# 7_can_rc_i2c_analog.net
KiCad netlist of a schematic drawn in Altium Designer
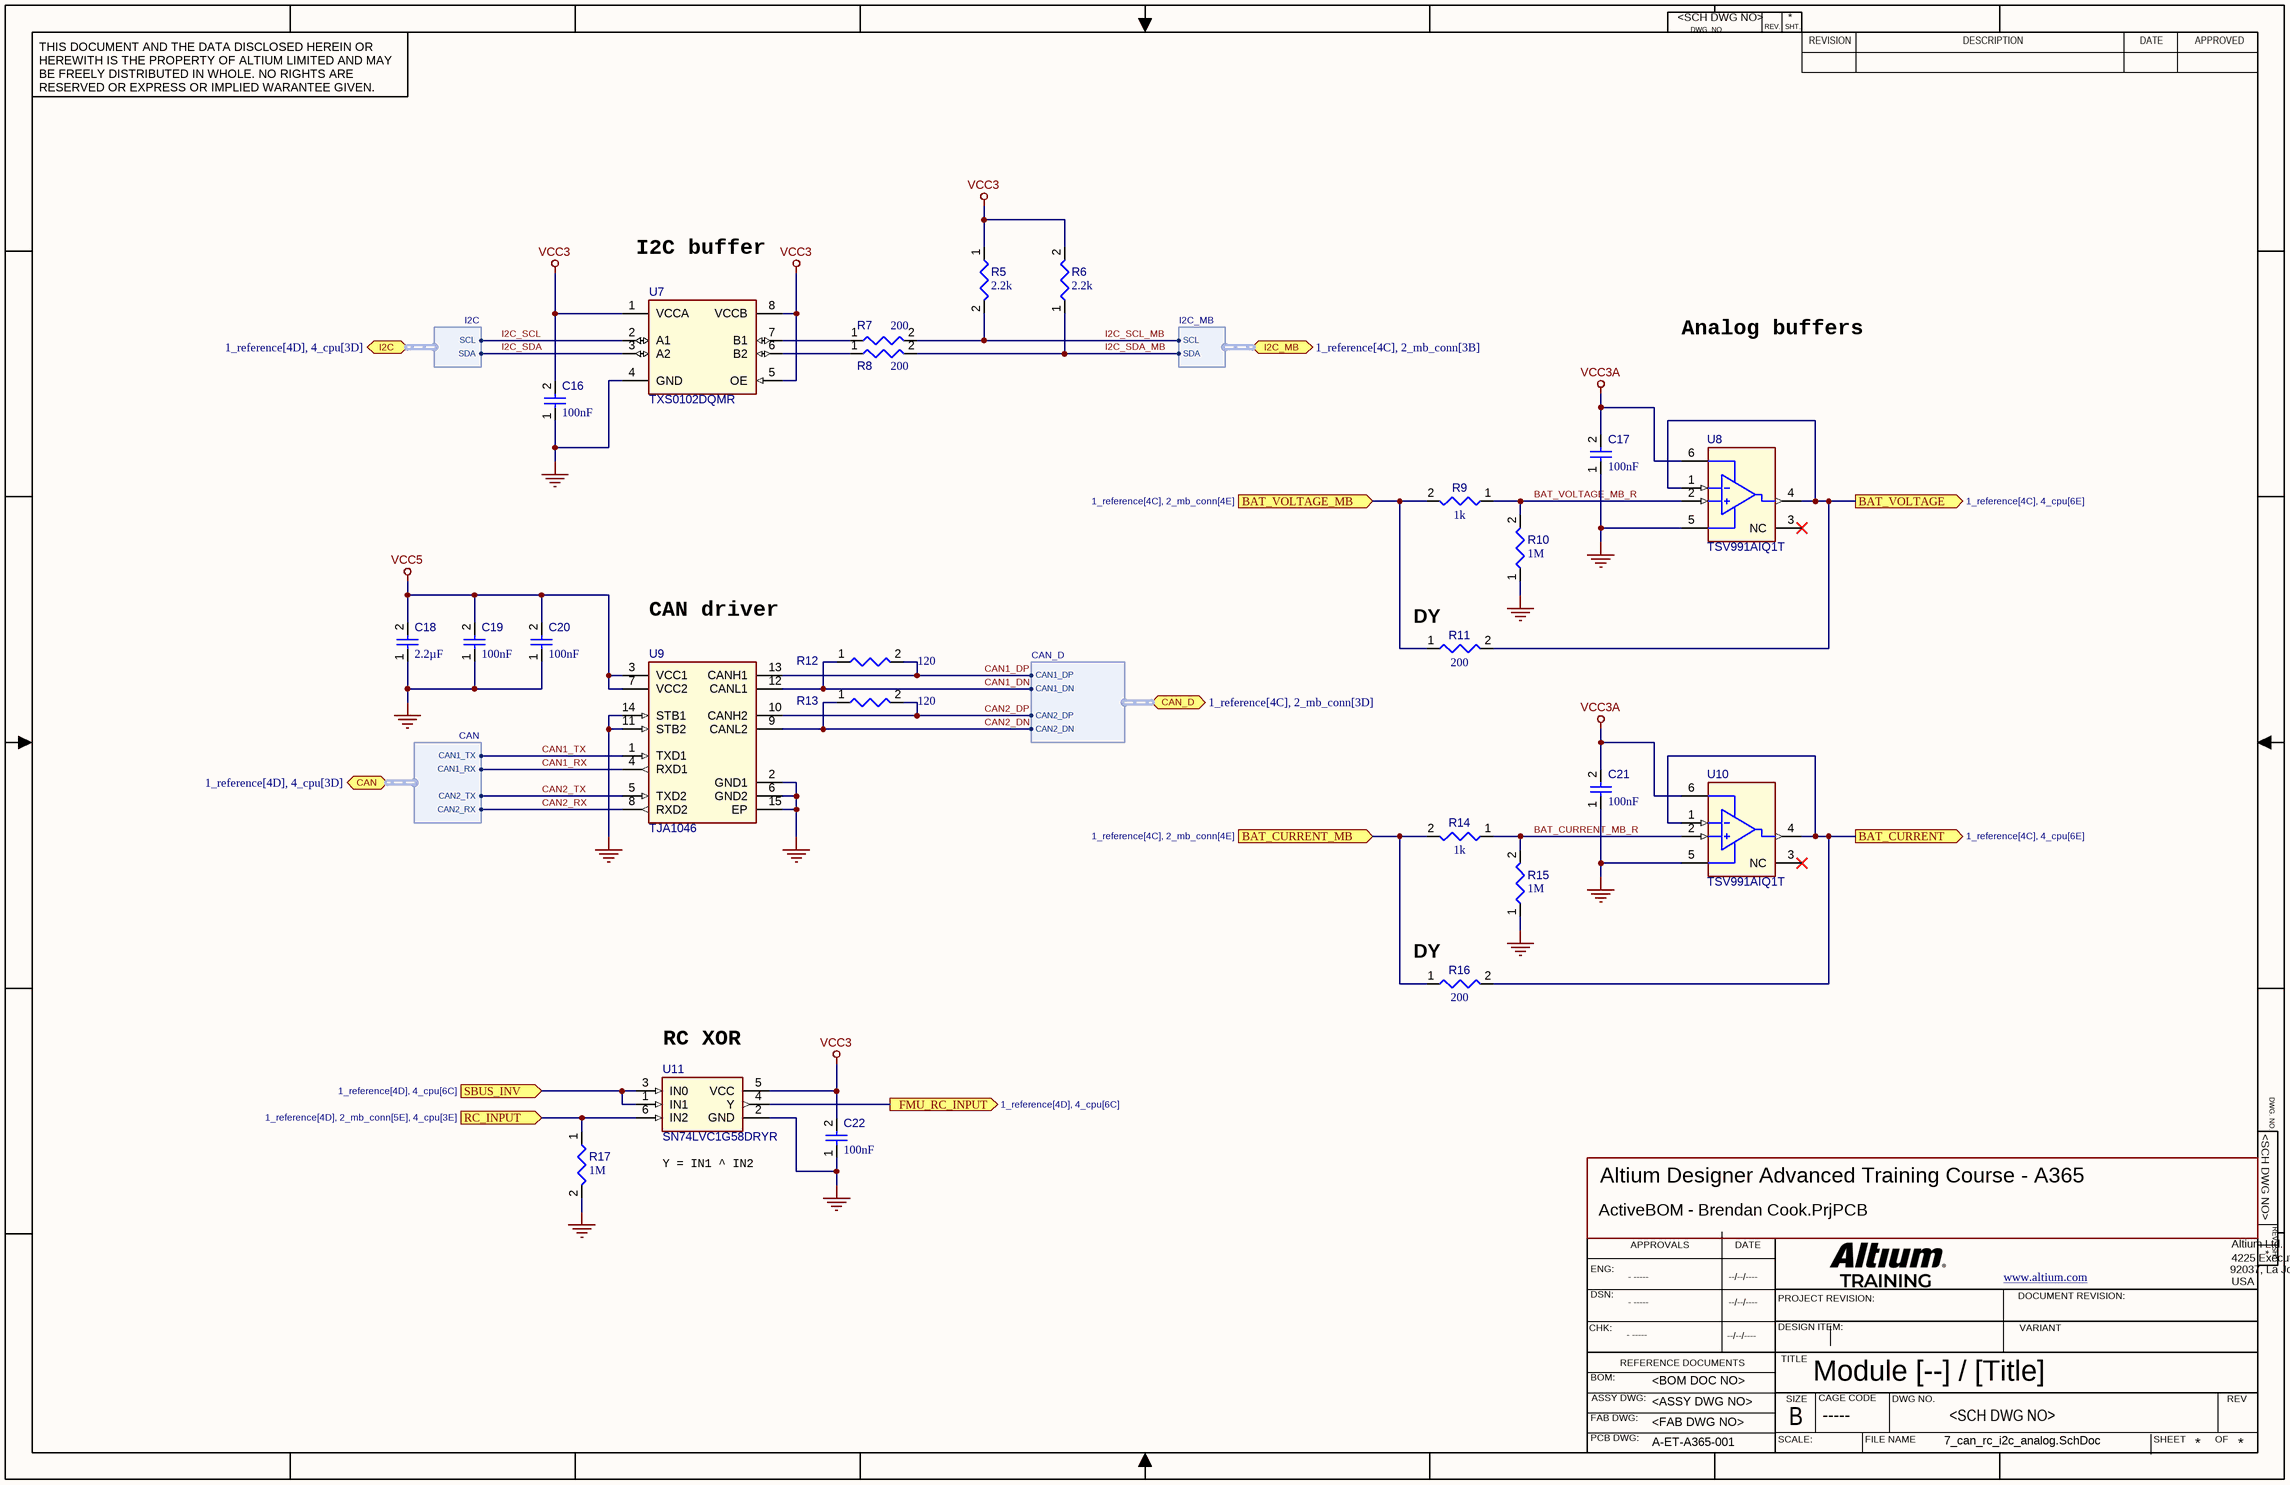
[diagram p0: 7_can_rc_i2c_analog.SchDoc]

(export (version "E")
  (design (tool "Eeschema 10.0.6"))
  (components
    (comp (ref "C16")
      (value "100nF")
      (footprint "CAPC0402(1005)60_L")
      (description "Chip Capacitor, 100nF +/-20%, 10V, 0402, Thickness 0.6 mm")
      (fields (field (name "TOLERANCE") "20%") (field (name "Comment") "Capacitor 100nF +/-20% 10V 0402"))
      (libsource (lib "MHH -  Altium Advanced Course A365 01") (part "CAP-NP-2"))
    )
    (comp (ref "C17")
      (value "100nF")
      (footprint "CAPC0402(1005)60_L")
      (description "Chip Capacitor, 100nF +/-20%, 10V, 0402, Thickness 0.6 mm")
      (fields (field (name "TOLERANCE") "20%") (field (name "Comment") "Capacitor 100nF +/-20% 10V 0402"))
      (libsource (lib "MHH -  Altium Advanced Course A365 01") (part "CAP-NP-2"))
    )
    (comp (ref "C18")
      (value "2.2µF")
      (footprint "CAPC0402(1005)60_L")
      (description "Chip Capacitor, 2,2µF +/-20%, 10V, 0402, Thickness 0.6 mm")
      (fields (field (name "TOLERANCE") "10%") (field (name "Comment") "Capacitor 2,2µF +/-20% 10V 0402"))
      (libsource (lib "MHH -  Altium Advanced Course A365 01") (part "CAP-NP-2"))
    )
    (comp (ref "C19")
      (value "100nF")
      (footprint "CAPC0402(1005)60_L")
      (description "Chip Capacitor, 100nF +/-20%, 10V, 0402, Thickness 0.6 mm")
      (fields (field (name "TOLERANCE") "20%") (field (name "Comment") "Capacitor 100nF +/-20% 10V 0402"))
      (libsource (lib "MHH -  Altium Advanced Course A365 01") (part "CAP-NP-2"))
    )
    (comp (ref "C20")
      (value "100nF")
      (footprint "CAPC0402(1005)60_L")
      (description "Chip Capacitor, 100nF +/-20%, 10V, 0402, Thickness 0.6 mm")
      (fields (field (name "TOLERANCE") "20%") (field (name "Comment") "Capacitor 100nF +/-20% 10V 0402"))
      (libsource (lib "MHH -  Altium Advanced Course A365 01") (part "CAP-NP-2"))
    )
    (comp (ref "C21")
      (value "100nF")
      (footprint "CAPC0402(1005)60_L")
      (description "Chip Capacitor, 100nF +/-20%, 10V, 0402, Thickness 0.6 mm")
      (fields (field (name "TOLERANCE") "20%") (field (name "Comment") "Capacitor 100nF +/-20% 10V 0402"))
      (libsource (lib "MHH -  Altium Advanced Course A365 01") (part "CAP-NP-2"))
    )
    (comp (ref "C22")
      (value "100nF")
      (footprint "CAPC0402(1005)60_L")
      (description "Chip Capacitor, 100nF +/-20%, 10V, 0402, Thickness 0.6 mm")
      (fields (field (name "TOLERANCE") "20%") (field (name "Comment") "Capacitor 100nF +/-20% 10V 0402"))
      (libsource (lib "MHH -  Altium Advanced Course A365 01") (part "CAP-NP-2"))
    )
    (comp (ref "R5")
      (value "2.2k")
      (footprint "RESC0402(1005)_L")
      (description "Chip Resistor, 2,2 kOhms, +/-5 %, 63 mW, -55 to 155 degC, 0402")
      (fields (field (name "POWER") "63mW") (field (name "TOLERANCE") "5%"))
      (libsource (lib "MHH -  Altium Advanced Course A365 01") (part "RES-2"))
    )
    (comp (ref "R6")
      (value "2.2k")
      (footprint "RESC0402(1005)_L")
      (description "Chip Resistor, 2,2 kOhms, +/-5 %, 63 mW, -55 to 155 degC, 0402")
      (fields (field (name "POWER") "63mW") (field (name "TOLERANCE") "5%"))
      (libsource (lib "MHH -  Altium Advanced Course A365 01") (part "RES-2"))
    )
    (comp (ref "R7")
      (value "200")
      (footprint "RESC0402(1005)_L")
      (description "Chip Resistor, 200 Ohms, +/-5 %, 63 mW, -55 to 155 degC, 0402")
      (fields (field (name "POWER") "63mW") (field (name "TOLERANCE") "5%"))
      (libsource (lib "MHH -  Altium Advanced Course A365 01") (part "RES-2"))
    )
    (comp (ref "R8")
      (value "200")
      (footprint "RESC0402(1005)_L")
      (description "Chip Resistor, 200 Ohms, +/-5 %, 63 mW, -55 to 155 degC, 0402")
      (fields (field (name "POWER") "63mW") (field (name "TOLERANCE") "5%"))
      (libsource (lib "MHH -  Altium Advanced Course A365 01") (part "RES-2"))
    )
    (comp (ref "R9")
      (value "1k")
      (footprint "RESC0402(1005)_L")
      (description "Chip Resistor, 1 kOhms, +/-5 %, 63 mW, -55 to 155 degC, 0402")
      (fields (field (name "TOLERANCE") "5%") (field (name "POWER") "63mW"))
      (libsource (lib "MHH -  Altium Advanced Course A365 01") (part "RES-2"))
    )
    (comp (ref "R10")
      (value "1M")
      (footprint "RESC0402(1005)_L")
      (description "Chip Resistor, 1 MOhms, +/-5 %, 63 mW, -55 to 155 degC, 0402")
      (fields (field (name "TOLERANCE") "5%") (field (name "POWER") "63mW"))
      (libsource (lib "MHH -  Altium Advanced Course A365 01") (part "RES-2"))
    )
    (comp (ref "R11")
      (value "200")
      (footprint "RESC0402(1005)_L")
      (description "Chip Resistor, 200 Ohms, +/-5 %, 63 mW, -55 to 155 degC, 0402")
      (fields (field (name "POWER") "63mW") (field (name "TOLERANCE") "5%"))
      (libsource (lib "MHH -  Altium Advanced Course A365 01") (part "RES-2"))
    )
    (comp (ref "R12")
      (value "120")
      (footprint "RESC0603(1608)_L")
      (description "Chip Resistor, 120 Ohms, +/-5 %, 0.1 W, -55 to 155 degC, 0603")
      (fields (field (name "TOLERANCE") "5%") (field (name "POWER") "100mW"))
      (libsource (lib "MHH -  Altium Advanced Course A365 01") (part "RES-2"))
    )
    (comp (ref "R13")
      (value "120")
      (footprint "RESC0603(1608)_L")
      (description "Chip Resistor, 120 Ohms, +/-5 %, 0.1 W, -55 to 155 degC, 0603")
      (fields (field (name "TOLERANCE") "5%") (field (name "POWER") "100mW"))
      (libsource (lib "MHH -  Altium Advanced Course A365 01") (part "RES-2"))
    )
    (comp (ref "R14")
      (value "1k")
      (footprint "RESC0402(1005)_L")
      (description "Chip Resistor, 1 kOhms, +/-5 %, 63 mW, -55 to 155 degC, 0402")
      (fields (field (name "TOLERANCE") "5%") (field (name "POWER") "63mW"))
      (libsource (lib "MHH -  Altium Advanced Course A365 01") (part "RES-2"))
    )
    (comp (ref "R15")
      (value "1M")
      (footprint "RESC0402(1005)_L")
      (description "Chip Resistor, 1 MOhms, +/-5 %, 63 mW, -55 to 155 degC, 0402")
      (fields (field (name "TOLERANCE") "5%") (field (name "POWER") "63mW"))
      (libsource (lib "MHH -  Altium Advanced Course A365 01") (part "RES-2"))
    )
    (comp (ref "R16")
      (value "200")
      (footprint "RESC0402(1005)_L")
      (description "Chip Resistor, 200 Ohms, +/-5 %, 63 mW, -55 to 155 degC, 0402")
      (fields (field (name "POWER") "63mW") (field (name "TOLERANCE") "5%"))
      (libsource (lib "MHH -  Altium Advanced Course A365 01") (part "RES-2"))
    )
    (comp (ref "R17")
      (value "1M")
      (footprint "RESC0402(1005)_L")
      (description "Chip Resistor, 1 MOhms, +/-5 %, 63 mW, -55 to 155 degC, 0402")
      (fields (field (name "TOLERANCE") "5%") (field (name "POWER") "63mW"))
      (libsource (lib "MHH -  Altium Advanced Course A365 01") (part "RES-2"))
    )
    (comp (ref "U7")
      (value "TXS0102DQMR")
      (footprint "DQM")
      (description "IC TRANSLATOR VOLTAGE 8-X2SON")
      (libsource (lib "MHH -  Altium Advanced Course A365 01") (part "CMP-001-0022-1"))
    )
    (comp (ref "U8")
      (value "TSV991AIQ1T")
      (footprint "STM-DFN-8_V")
      (libsource (lib "MHH -  Altium Advanced Course A365 01") (part "CMP-001-0008-5"))
    )
    (comp (ref "U9")
      (value "TJA1046")
      (footprint "NXP-SOT1086-2_L")
      (libsource (lib "MHH -  Altium Advanced Course A365 01") (part "CMP-00180-5"))
    )
    (comp (ref "U10")
      (value "TSV991AIQ1T")
      (footprint "STM-DFN-8_V")
      (libsource (lib "MHH -  Altium Advanced Course A365 01") (part "CMP-001-0008-5"))
    )
    (comp (ref "U11")
      (value "SN74LVC1G58DRYR")
      (footprint "DRY0006A_V")
      (description "CONFIGURABLE MULTIPLE-FUNCTION GATE, DRY0006A, LARGE T&R")
      (libsource (lib "MHH -  Altium Advanced Course A365 01") (part "CMP-00132-5"))
    )
  )
  (nets
    (net (code "5") (name "/BAT_CURRENT") (class "Default")
      (node (ref "R16") (pin "2") (pinfunction "2_2") (pintype "passive"))
      (node (ref "U10") (pin "1") (pinfunction "IN-_1") (pintype "input"))
      (node (ref "U10") (pin "4") (pinfunction "OUT_4") (pintype "output"))
    )
    (net (code "6") (name "/BAT_CURRENT_MB") (class "Default")
      (node (ref "R14") (pin "2") (pinfunction "2_2") (pintype "passive"))
      (node (ref "R16") (pin "1") (pinfunction "1_1") (pintype "passive"))
    )
    (net (code "7") (name "/BAT_CURRENT_MB_R") (class "Default")
      (node (ref "R14") (pin "1") (pinfunction "1_1") (pintype "passive"))
      (node (ref "R15") (pin "2") (pinfunction "2_2") (pintype "passive"))
      (node (ref "U10") (pin "2") (pinfunction "IN+_2") (pintype "input"))
    )
    (net (code "8") (name "/BAT_VOLTAGE") (class "Default")
      (node (ref "R11") (pin "2") (pinfunction "2_2") (pintype "passive"))
      (node (ref "U8") (pin "1") (pinfunction "IN-_1") (pintype "input"))
      (node (ref "U8") (pin "4") (pinfunction "OUT_4") (pintype "output"))
    )
    (net (code "9") (name "/BAT_VOLTAGE_MB") (class "Default")
      (node (ref "R11") (pin "1") (pinfunction "1_1") (pintype "passive"))
      (node (ref "R9") (pin "2") (pinfunction "2_2") (pintype "passive"))
    )
    (net (code "10") (name "/BAT_VOLTAGE_MB_R") (class "Default")
      (node (ref "R10") (pin "2") (pinfunction "2_2") (pintype "passive"))
      (node (ref "R9") (pin "1") (pinfunction "1_1") (pintype "passive"))
      (node (ref "U8") (pin "2") (pinfunction "IN+_2") (pintype "input"))
    )
    (net (code "11") (name "/CAN1_DN") (class "Default")
      (node (ref "R12") (pin "1") (pinfunction "1_1") (pintype "passive"))
      (node (ref "U9") (pin "12") (pinfunction "CANL1_12") (pintype "passive"))
    )
    (net (code "12") (name "/CAN1_DP") (class "Default")
      (node (ref "R12") (pin "2") (pinfunction "2_2") (pintype "passive"))
      (node (ref "U9") (pin "13") (pinfunction "CANH1_13") (pintype "passive"))
    )
    (net (code "13") (name "/CAN1_RX") (class "Default")
      (node (ref "U9") (pin "4") (pinfunction "RXD1_4") (pintype "output"))
    )
    (net (code "14") (name "/CAN1_TX") (class "Default")
      (node (ref "U9") (pin "1") (pinfunction "TXD1_1") (pintype "input"))
    )
    (net (code "15") (name "/CAN2_DN") (class "Default")
      (node (ref "R13") (pin "1") (pinfunction "1_1") (pintype "passive"))
      (node (ref "U9") (pin "9") (pinfunction "CANL2_9") (pintype "passive"))
    )
    (net (code "16") (name "/CAN2_DP") (class "Default")
      (node (ref "R13") (pin "2") (pinfunction "2_2") (pintype "passive"))
      (node (ref "U9") (pin "10") (pinfunction "CANH2_10") (pintype "passive"))
    )
    (net (code "17") (name "/CAN2_RX") (class "Default")
      (node (ref "U9") (pin "8") (pinfunction "RXD2_8") (pintype "output"))
    )
    (net (code "18") (name "/CAN2_TX") (class "Default")
      (node (ref "U9") (pin "5") (pinfunction "TXD2_5") (pintype "input"))
    )
    (net (code "19") (name "/FMU_RC_INPUT") (class "Default")
      (node (ref "U11") (pin "4") (pinfunction "Y_4") (pintype "output"))
    )
    (net (code "20") (name "/I2C_SCL") (class "Default")
      (node (ref "U7") (pin "2") (pinfunction "A1_2") (pintype "bidirectional"))
    )
    (net (code "21") (name "/I2C_SCL_MB") (class "Default")
      (node (ref "R5") (pin "2") (pinfunction "2_2") (pintype "passive"))
      (node (ref "R7") (pin "2") (pinfunction "2_2") (pintype "passive"))
    )
    (net (code "22") (name "/I2C_SDA") (class "Default")
      (node (ref "U7") (pin "3") (pinfunction "A2_3") (pintype "bidirectional"))
    )
    (net (code "23") (name "/I2C_SDA_MB") (class "Default")
      (node (ref "R6") (pin "1") (pinfunction "1_1") (pintype "passive"))
      (node (ref "R8") (pin "2") (pinfunction "2_2") (pintype "passive"))
    )
    (net (code "24") (name "/RC_INPUT") (class "Default")
      (node (ref "R17") (pin "1") (pinfunction "1_1") (pintype "passive"))
      (node (ref "U11") (pin "6") (pinfunction "IN2_6") (pintype "input"))
    )
    (net (code "25") (name "/SBUS_INV") (class "Default")
      (node (ref "U11") (pin "1") (pinfunction "IN1_1") (pintype "input"))
      (node (ref "U11") (pin "3") (pinfunction "IN0_3") (pintype "input"))
    )
    (net (code "30") (name "GND") (class "Default")
      (node (ref "C16") (pin "1") (pinfunction "1_1") (pintype "passive"))
      (node (ref "C17") (pin "1") (pinfunction "1_1") (pintype "passive"))
      (node (ref "C18") (pin "1") (pinfunction "1_1") (pintype "passive"))
      (node (ref "C19") (pin "1") (pinfunction "1_1") (pintype "passive"))
      (node (ref "C20") (pin "1") (pinfunction "1_1") (pintype "passive"))
      (node (ref "C21") (pin "1") (pinfunction "1_1") (pintype "passive"))
      (node (ref "C22") (pin "1") (pinfunction "1_1") (pintype "passive"))
      (node (ref "R10") (pin "1") (pinfunction "1_1") (pintype "passive"))
      (node (ref "R15") (pin "1") (pinfunction "1_1") (pintype "passive"))
      (node (ref "R17") (pin "2") (pinfunction "2_2") (pintype "passive"))
      (node (ref "U10") (pin "5") (pinfunction "VCC-_5") (pintype "power_in"))
      (node (ref "U11") (pin "2") (pinfunction "GND_2") (pintype "power_in"))
      (node (ref "U7") (pin "4") (pinfunction "GND_4") (pintype "power_in"))
      (node (ref "U8") (pin "5") (pinfunction "VCC-_5") (pintype "power_in"))
      (node (ref "U9") (pin "11") (pinfunction "STB2_11") (pintype "input"))
      (node (ref "U9") (pin "14") (pinfunction "STB1_14") (pintype "input"))
      (node (ref "U9") (pin "15") (pinfunction "EP_15") (pintype "power_in"))
      (node (ref "U9") (pin "2") (pinfunction "GND1_2") (pintype "power_in"))
      (node (ref "U9") (pin "6") (pinfunction "GND2_6") (pintype "power_in"))
    )
    (net (code "31") (name "Net-(U7-B1)") (class "Default")
      (node (ref "R7") (pin "1") (pinfunction "1_1") (pintype "passive"))
      (node (ref "U7") (pin "7") (pinfunction "B1_7") (pintype "bidirectional"))
    )
    (net (code "32") (name "Net-(U7-B2)") (class "Default")
      (node (ref "R8") (pin "1") (pinfunction "1_1") (pintype "passive"))
      (node (ref "U7") (pin "6") (pinfunction "B2_6") (pintype "bidirectional"))
    )
    (net (code "33") (name "VCC3") (class "Default")
      (node (ref "C16") (pin "2") (pinfunction "2_2") (pintype "passive"))
      (node (ref "C22") (pin "2") (pinfunction "2_2") (pintype "passive"))
      (node (ref "R5") (pin "1") (pinfunction "1_1") (pintype "passive"))
      (node (ref "R6") (pin "2") (pinfunction "2_2") (pintype "passive"))
      (node (ref "U11") (pin "5") (pinfunction "VCC_5") (pintype "power_in"))
      (node (ref "U7") (pin "1") (pinfunction "VCCA_1") (pintype "power_in"))
      (node (ref "U7") (pin "5") (pinfunction "OE_5") (pintype "input"))
      (node (ref "U7") (pin "8") (pinfunction "VCCB_8") (pintype "power_in"))
    )
    (net (code "34") (name "VCC3A") (class "Default")
      (node (ref "C17") (pin "2") (pinfunction "2_2") (pintype "passive"))
      (node (ref "C21") (pin "2") (pinfunction "2_2") (pintype "passive"))
      (node (ref "U10") (pin "6") (pinfunction "VCC+_6") (pintype "power_in"))
      (node (ref "U8") (pin "6") (pinfunction "VCC+_6") (pintype "power_in"))
    )
    (net (code "35") (name "VCC5") (class "Default")
      (node (ref "C18") (pin "2") (pinfunction "2_2") (pintype "passive"))
      (node (ref "C19") (pin "2") (pinfunction "2_2") (pintype "passive"))
      (node (ref "C20") (pin "2") (pinfunction "2_2") (pintype "passive"))
      (node (ref "U9") (pin "3") (pinfunction "VCC1_3") (pintype "power_in"))
      (node (ref "U9") (pin "7") (pinfunction "VCC2_7") (pintype "power_in"))
    )
    (net (code "36") (name "unconnected-(U8-NC-Pad3)") (class "Default")
      (node (ref "U8") (pin "3") (pinfunction "NC_3") (pintype "passive+no_connect"))
    )
    (net (code "37") (name "unconnected-(U10-NC-Pad3)") (class "Default")
      (node (ref "U10") (pin "3") (pinfunction "NC_3") (pintype "passive+no_connect"))
    )
  )
)
